# os20_newenc.net
KiCad netlist of a schematic drawn in EAGLE
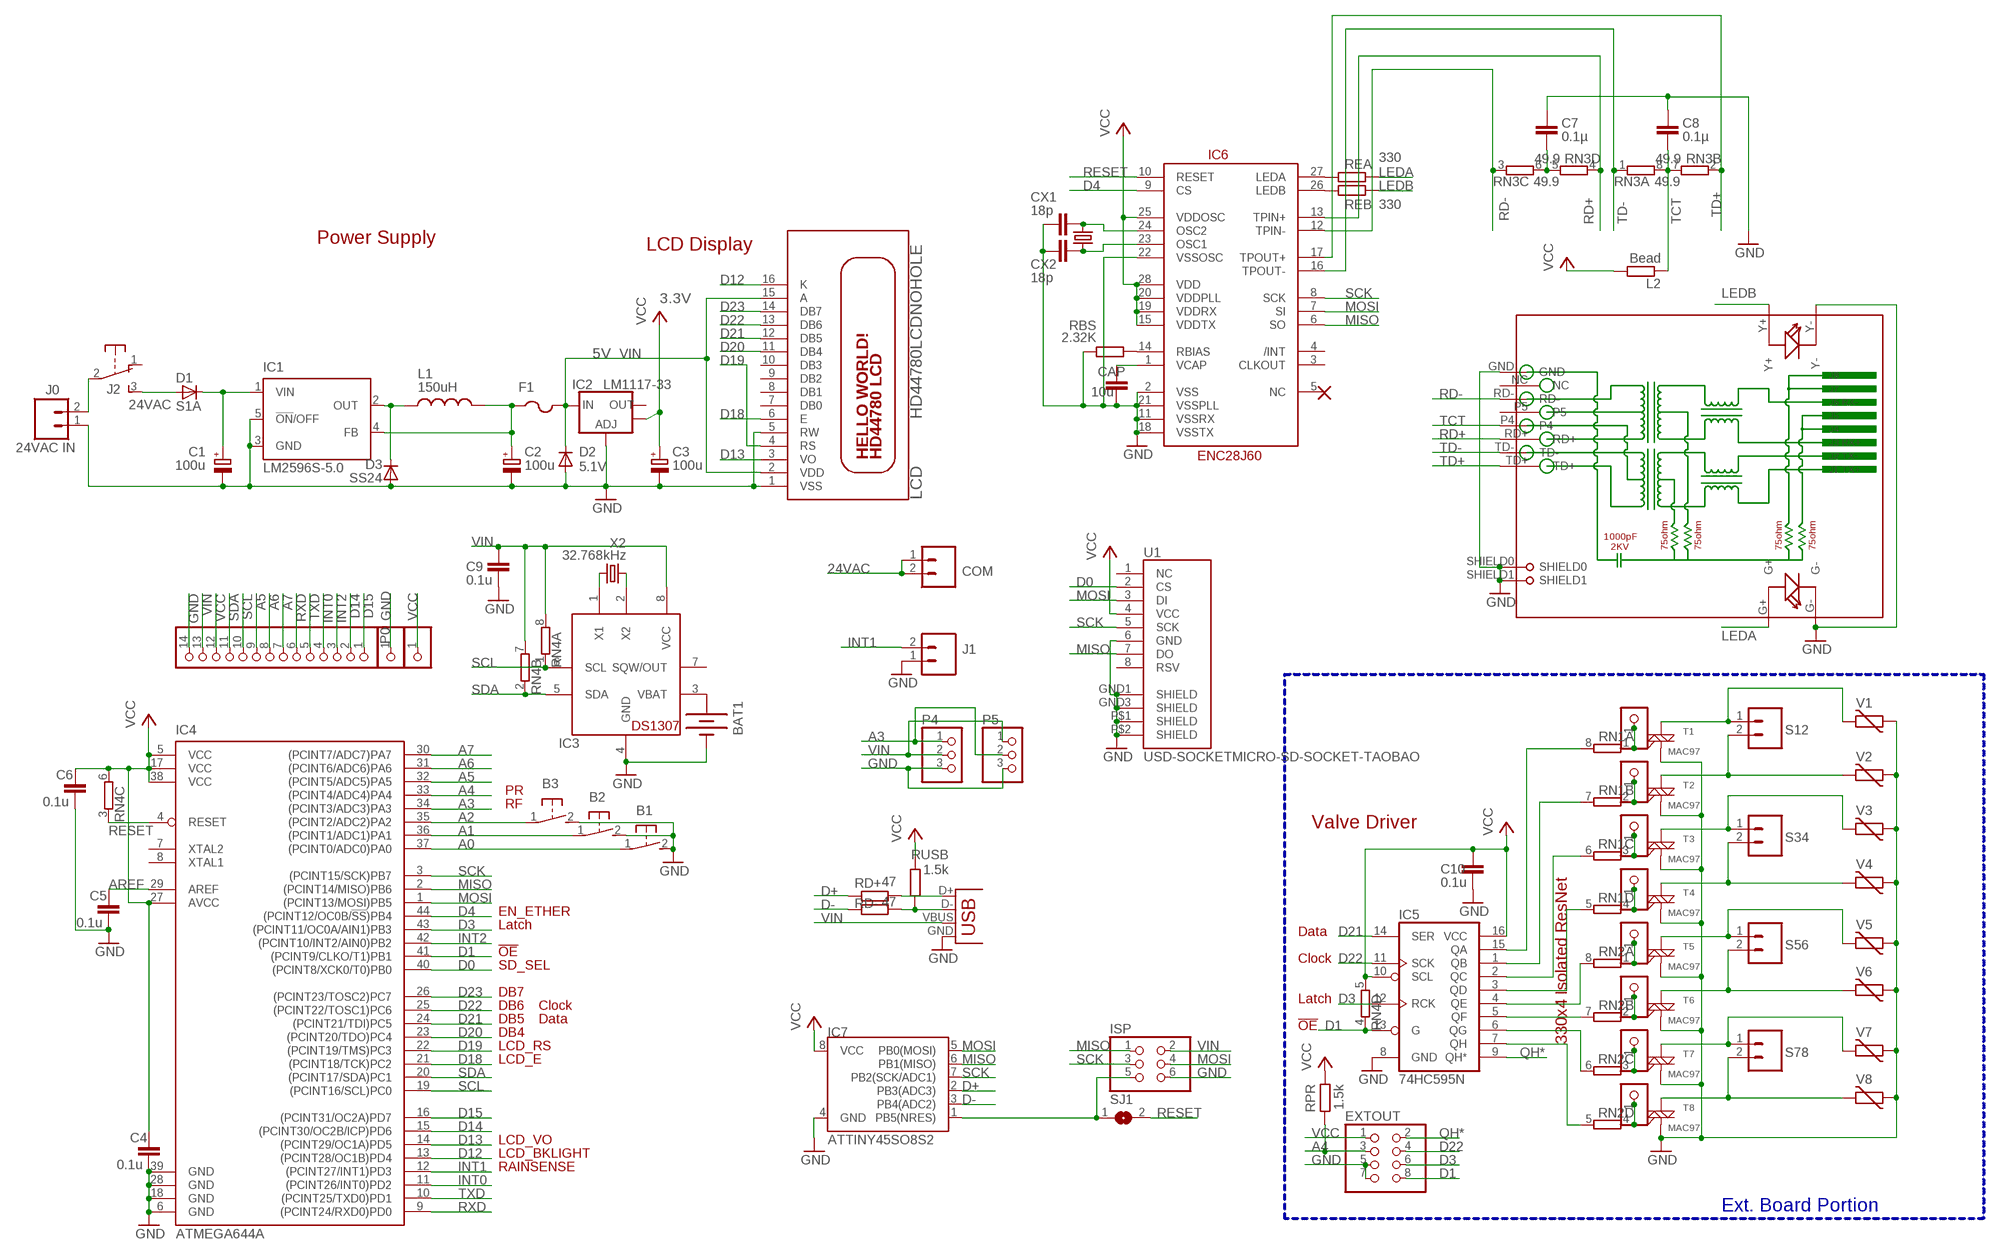
[diagram p0: schematic, sheet 1]

(export (version "E")
  (design (tool "Eeschema 10.0.6"))
  (components
    (comp (ref "B1")
      (value "31-XX")
      (footprint "eagle-import:B3F-31XX")
      (libsource (lib "eagle-import") (part "31-XX"))
    )
    (comp (ref "B2")
      (value "31-XX")
      (footprint "eagle-import:B3F-31XX")
      (libsource (lib "eagle-import") (part "31-XX"))
    )
    (comp (ref "B3")
      (value "31-XX")
      (footprint "eagle-import:B3F-31XX")
      (libsource (lib "eagle-import") (part "31-XX"))
    )
    (comp (ref "BAT1")
      (value "BATTERYBATTERY_12MM_SMT")
      (footprint "eagle-import:BATTCON_12MM_SMT")
      (libsource (lib "eagle-import") (part "BATTERYBATTERY_12MM_SMT"))
    )
    (comp (ref "C1")
      (value "100u")
      (footprint "eagle-import:E3,5-8")
      (libsource (lib "eagle-import") (part "CPOL-EUE3.5-8"))
    )
    (comp (ref "C2")
      (value "100u")
      (footprint "eagle-import:PANASONIC_D")
      (libsource (lib "eagle-import") (part "CPOL-EUD"))
    )
    (comp (ref "C3")
      (value "100u")
      (footprint "eagle-import:PANASONIC_D")
      (libsource (lib "eagle-import") (part "CPOL-EUD"))
    )
    (comp (ref "C4")
      (value "0.1u")
      (footprint "eagle-import:C0805")
      (libsource (lib "eagle-import") (part "C-EUC0805"))
    )
    (comp (ref "C5")
      (value "0.1u")
      (footprint "eagle-import:C0805")
      (libsource (lib "eagle-import") (part "C-EUC0805"))
    )
    (comp (ref "C6")
      (value "0.1u")
      (footprint "eagle-import:C0805")
      (libsource (lib "eagle-import") (part "C-EUC0805"))
    )
    (comp (ref "C7")
      (value "0.1µ")
      (footprint "eagle-import:C0805")
      (libsource (lib "eagle-import") (part "resistor_C-EUC0805"))
    )
    (comp (ref "C8")
      (value "0.1µ")
      (footprint "eagle-import:C0805")
      (libsource (lib "eagle-import") (part "resistor_C-EUC0805"))
    )
    (comp (ref "C9")
      (value "0.1u")
      (footprint "eagle-import:C0805")
      (libsource (lib "eagle-import") (part "C-EUC0805"))
    )
    (comp (ref "C10")
      (value "0.1u")
      (footprint "eagle-import:C0805")
      (libsource (lib "eagle-import") (part "C-EUC0805"))
    )
    (comp (ref "CAP")
      (value "10u")
      (footprint "eagle-import:C0805")
      (libsource (lib "eagle-import") (part "resistor_C-EUC0805"))
    )
    (comp (ref "COM")
      (value "M025MM")
      (footprint "eagle-import:SCREWTERMINAL-5MM-2")
      (libsource (lib "eagle-import") (part "M025MM"))
    )
    (comp (ref "CX1")
      (value "18p")
      (footprint "eagle-import:C0805")
      (libsource (lib "eagle-import") (part "resistor_C-EUC0805"))
    )
    (comp (ref "CX2")
      (value "18p")
      (footprint "eagle-import:C0805")
      (libsource (lib "eagle-import") (part "resistor_C-EUC0805"))
    )
    (comp (ref "D1")
      (value "S1A")
      (footprint "eagle-import:DO-214AC")
      (libsource (lib "eagle-import") (part "DIODE-DO-214AC"))
    )
    (comp (ref "D2")
      (value "5.1V")
      (footprint "eagle-import:MINIMELF")
      (libsource (lib "eagle-import") (part "DIODE-MINIMELF"))
    )
    (comp (ref "D3")
      (value "SS24")
      (footprint "eagle-import:DO-214AC")
      (libsource (lib "eagle-import") (part "DIODE-DO-214AC"))
    )
    (comp (ref "EXTOUT")
      (value "PINHD-2X4")
      (footprint "eagle-import:2X04")
      (libsource (lib "eagle-import") (part "PINHD-2X4"))
    )
    (comp (ref "F1")
      (value "PTCFUSE-1812")
      (footprint "eagle-import:1812")
      (libsource (lib "eagle-import") (part "PTCFUSE-1812"))
    )
    (comp (ref "IC1")
      (value "LM2596S-5.0")
      (footprint "eagle-import:TO263-5")
      (fields (field (name "MF") "NATIONAL SEMICONDUCTOR") (field (name "MPN") "LM2596S-ADJ/NOPB"))
      (libsource (lib "eagle-import") (part "LM2596S"))
    )
    (comp (ref "IC2")
      (value "LM1117-33")
      (footprint "eagle-import:SOT223")
      (libsource (lib "eagle-import") (part "V_REG_LM1117SOT223"))
    )
    (comp (ref "IC3")
      (value "DS1307")
      (footprint "eagle-import:SO08")
      (libsource (lib "eagle-import") (part "DS1307SOIC"))
    )
    (comp (ref "IC4")
      (value "ATMEGA644A")
      (footprint "eagle-import:TQFP44")
      (fields (field (name "MPN") "ATMEGA644PV-10AU"))
      (libsource (lib "eagle-import") (part "ATMEGA644A"))
    )
    (comp (ref "IC5")
      (value "74HC595N")
      (footprint "eagle-import:SO16")
      (libsource (lib "eagle-import") (part "74595DLS"))
    )
    (comp (ref "IC6")
      (value "ENC28J60")
      (footprint "eagle-import:SOIC28WLONG")
      (libsource (lib "eagle-import") (part "ENC28J60SO28LONG"))
    )
    (comp (ref "IC7")
      (value "ATTINY45SO8S2")
      (footprint "eagle-import:SO8S2")
      (libsource (lib "eagle-import") (part "ATTINY45SO8S2"))
    )
    (comp (ref "ISP")
      (value "PINHD-2X3")
      (footprint "eagle-import:2X03")
      (libsource (lib "eagle-import") (part "PINHD-2X3"))
    )
    (comp (ref "J0")
      (value "24VAC IN")
      (footprint "eagle-import:SCREWTERMINAL-5MM-2")
      (libsource (lib "eagle-import") (part "M025MM"))
    )
    (comp (ref "J1")
      (value "M025MM")
      (footprint "eagle-import:SCREWTERMINAL-5MM-2")
      (libsource (lib "eagle-import") (part "M025MM"))
    )
    (comp (ref "J2")
      (value "EG1206")
      (footprint "eagle-import:EG1206")
      (libsource (lib "eagle-import") (part "EG1206"))
    )
    (comp (ref "JP2")
      (value "PINHD-1X1CB")
      (footprint "eagle-import:1X01-CLEANBIG")
      (libsource (lib "eagle-import") (part "PINHD-1X1CB"))
    )
    (comp (ref "JP3")
      (value "PINHD-1X1CB")
      (footprint "eagle-import:1X01-CLEANBIG")
      (libsource (lib "eagle-import") (part "PINHD-1X1CB"))
    )
    (comp (ref "JP4")
      (value "PINHD-1X1CB")
      (footprint "eagle-import:1X01-CLEANBIG")
      (libsource (lib "eagle-import") (part "PINHD-1X1CB"))
    )
    (comp (ref "JP5")
      (value "PINHD-1X1CB")
      (footprint "eagle-import:1X01-CLEANBIG")
      (libsource (lib "eagle-import") (part "PINHD-1X1CB"))
    )
    (comp (ref "JP6")
      (value "PINHD-1X1CB")
      (footprint "eagle-import:1X01-CLEANBIG")
      (libsource (lib "eagle-import") (part "PINHD-1X1CB"))
    )
    (comp (ref "JP7")
      (value "PINHD-1X1CB")
      (footprint "eagle-import:1X01-CLEANBIG")
      (libsource (lib "eagle-import") (part "PINHD-1X1CB"))
    )
    (comp (ref "JP8")
      (value "PINHD-1X1CB")
      (footprint "eagle-import:1X01-CLEANBIG")
      (libsource (lib "eagle-import") (part "PINHD-1X1CB"))
    )
    (comp (ref "JP9")
      (value "PINHD-1X1CB")
      (footprint "eagle-import:1X01-CLEANBIG")
      (libsource (lib "eagle-import") (part "PINHD-1X1CB"))
    )
    (comp (ref "L1")
      (value "150uH")
      (footprint "eagle-import:CDRH125")
      (libsource (lib "eagle-import") (part "INDUCTORPWR"))
    )
    (comp (ref "L2")
      (value "Bead")
      (footprint "eagle-import:R0805")
      (libsource (lib "eagle-import") (part "R-EU_R0805"))
    )
    (comp (ref "LCD")
      (value "HD44780LCDNOHOLE")
      (footprint "eagle-import:LCD1602A")
      (libsource (lib "eagle-import") (part "HD44780LCDNOHOLE"))
    )
    (comp (ref "P0")
      (value "PINHD-1X14-CB")
      (footprint "eagle-import:1X14-CB")
      (libsource (lib "eagle-import") (part "PINHD-1X14-CB"))
    )
    (comp (ref "P1")
      (value "PINHD-1X1CB")
      (footprint "eagle-import:1X01-CLEANBIG")
      (libsource (lib "eagle-import") (part "PINHD-1X1CB"))
    )
    (comp (ref "P2")
      (value "PINHD-1X1CB")
      (footprint "eagle-import:1X01-CLEANBIG")
      (libsource (lib "eagle-import") (part "PINHD-1X1CB"))
    )
    (comp (ref "P4")
      (value "PINHD-1X3")
      (footprint "eagle-import:1X03")
      (libsource (lib "eagle-import") (part "PINHD-1X3"))
    )
    (comp (ref "P5")
      (value "PINHD-1X3")
      (footprint "eagle-import:1X03")
      (libsource (lib "eagle-import") (part "PINHD-1X3"))
    )
    (comp (ref "RBS")
      (value "2.32K")
      (footprint "eagle-import:R0805")
      (libsource (lib "eagle-import") (part "R-EU_R0805"))
    )
    (comp (ref "RD+")
      (value "47")
      (footprint "eagle-import:R0805")
      (libsource (lib "eagle-import") (part "R-EU_R0805"))
    )
    (comp (ref "RD-")
      (value "47")
      (footprint "eagle-import:R0805")
      (libsource (lib "eagle-import") (part "R-EU_R0805"))
    )
    (comp (ref "REA")
      (value "330")
      (footprint "eagle-import:R0805")
      (libsource (lib "eagle-import") (part "R-EU_R0805"))
    )
    (comp (ref "REB")
      (value "330")
      (footprint "eagle-import:R0805")
      (libsource (lib "eagle-import") (part "R-EU_R0805"))
    )
    (comp (ref "RJ45")
      (value "HR911105A")
      (footprint "eagle-import:HR911105A")
      (libsource (lib "eagle-import") (part "HR911105A"))
    )
    (comp (ref "RN1")
      (value "4R-NEXB38V")
      (footprint "eagle-import:EXB38V")
      (libsource (lib "eagle-import") (part "4R-NEXB38V"))
    )
    (comp (ref "RN2")
      (value "4R-NEXB38V")
      (footprint "eagle-import:EXB38V")
      (libsource (lib "eagle-import") (part "4R-NEXB38V"))
    )
    (comp (ref "RN3")
      (value "49.9")
      (footprint "eagle-import:EXB38V")
      (libsource (lib "eagle-import") (part "4R-NEXB38V"))
    )
    (comp (ref "RN4")
      (value "4R-NEXB38V")
      (footprint "eagle-import:EXB38V")
      (libsource (lib "eagle-import") (part "4R-NEXB38V"))
    )
    (comp (ref "RPR")
      (value "1.5k")
      (footprint "eagle-import:R0805")
      (libsource (lib "eagle-import") (part "R-EU_R0805"))
    )
    (comp (ref "RUSB")
      (value "1.5k")
      (footprint "eagle-import:R0805")
      (libsource (lib "eagle-import") (part "R-EU_R0805"))
    )
    (comp (ref "S12")
      (value "M025MM")
      (footprint "eagle-import:SCREWTERMINAL-5MM-2")
      (libsource (lib "eagle-import") (part "M025MM"))
    )
    (comp (ref "S34")
      (value "M025MM")
      (footprint "eagle-import:SCREWTERMINAL-5MM-2")
      (libsource (lib "eagle-import") (part "M025MM"))
    )
    (comp (ref "S56")
      (value "M025MM")
      (footprint "eagle-import:SCREWTERMINAL-5MM-2")
      (libsource (lib "eagle-import") (part "M025MM"))
    )
    (comp (ref "S78")
      (value "M025MM")
      (footprint "eagle-import:SCREWTERMINAL-5MM-2")
      (libsource (lib "eagle-import") (part "M025MM"))
    )
    (comp (ref "SJ1") (value "SJ") (footprint "eagle-import:SJ") (libsource (lib "eagle-import") (part "SJ")))
    (comp (ref "T1")
      (value "MAC97")
      (footprint "eagle-import:SOT223")
      (libsource (lib "eagle-import") (part "MAC97SOT223"))
    )
    (comp (ref "T2")
      (value "MAC97")
      (footprint "eagle-import:SOT223")
      (libsource (lib "eagle-import") (part "MAC97SOT223"))
    )
    (comp (ref "T3")
      (value "MAC97")
      (footprint "eagle-import:SOT223")
      (libsource (lib "eagle-import") (part "MAC97SOT223"))
    )
    (comp (ref "T4")
      (value "MAC97")
      (footprint "eagle-import:SOT223")
      (libsource (lib "eagle-import") (part "MAC97SOT223"))
    )
    (comp (ref "T5")
      (value "MAC97")
      (footprint "eagle-import:SOT223")
      (libsource (lib "eagle-import") (part "MAC97SOT223"))
    )
    (comp (ref "T6")
      (value "MAC97")
      (footprint "eagle-import:SOT223")
      (libsource (lib "eagle-import") (part "MAC97SOT223"))
    )
    (comp (ref "T7")
      (value "MAC97")
      (footprint "eagle-import:SOT223")
      (libsource (lib "eagle-import") (part "MAC97SOT223"))
    )
    (comp (ref "T8")
      (value "MAC97")
      (footprint "eagle-import:SOT223")
      (libsource (lib "eagle-import") (part "MAC97SOT223"))
    )
    (comp (ref "U1")
      (value "USD-SOCKETMICRO-SD-SOCKET-TAOBAO")
      (footprint "eagle-import:MICRO-SD-SOCKET-TAOBAO")
      (libsource (lib "eagle-import") (part "USD-SOCKETMICRO-SD-SOCKET-TAOBAO"))
    )
    (comp (ref "USB")
      (value "USBPTH")
      (footprint "eagle-import:USB-B-PTH")
      (libsource (lib "eagle-import") (part "USBPTH"))
    )
    (comp (ref "V1")
      (value "MOV")
      (footprint "eagle-import:R-5")
      (libsource (lib "eagle-import") (part "VARISTOR-5"))
    )
    (comp (ref "V2")
      (value "MOV")
      (footprint "eagle-import:R-5")
      (libsource (lib "eagle-import") (part "VARISTOR-5"))
    )
    (comp (ref "V3")
      (value "MOV")
      (footprint "eagle-import:R-5")
      (libsource (lib "eagle-import") (part "VARISTOR-5"))
    )
    (comp (ref "V4")
      (value "MOV")
      (footprint "eagle-import:R-5")
      (libsource (lib "eagle-import") (part "VARISTOR-5"))
    )
    (comp (ref "V5")
      (value "MOV")
      (footprint "eagle-import:R-5")
      (libsource (lib "eagle-import") (part "VARISTOR-5"))
    )
    (comp (ref "V6")
      (value "MOV")
      (footprint "eagle-import:R-5")
      (libsource (lib "eagle-import") (part "VARISTOR-5"))
    )
    (comp (ref "V7")
      (value "MOV")
      (footprint "eagle-import:R-5")
      (libsource (lib "eagle-import") (part "VARISTOR-5"))
    )
    (comp (ref "V8")
      (value "MOV")
      (footprint "eagle-import:R-5")
      (libsource (lib "eagle-import") (part "VARISTOR-5"))
    )
    (comp (ref "X1")
      (value "25MHz")
      (footprint "eagle-import:HC49US")
      (libsource (lib "eagle-import") (part "CRYSTALHC49US"))
    )
    (comp (ref "X2")
      (value "32.768kHz")
      (footprint "eagle-import:TC26H")
      (libsource (lib "eagle-import") (part "crystal_CRYSTALTC26H"))
    )
  )
  (nets
    (net (code "1") (name "/24VAC") (class "Default")
      (node (ref "COM") (pin "1") (pinfunction "1_1") (pintype "passive"))
      (node (ref "COM") (pin "2") (pinfunction "2_2") (pintype "passive"))
      (node (ref "D1") (pin "A") (pinfunction "A_A") (pintype "passive"))
      (node (ref "J2") (pin "3") (pinfunction "S_3") (pintype "passive"))
    )
    (net (code "2") (name "/A0") (class "Default")
      (node (ref "B1") (pin "1") (pinfunction "P_1") (pintype "passive"))
      (node (ref "IC4") (pin "37") (pinfunction "(PCINT0/ADC0)PA0_37") (pintype "bidirectional"))
    )
    (net (code "3") (name "/A1") (class "Default")
      (node (ref "B2") (pin "1") (pinfunction "P_1") (pintype "passive"))
      (node (ref "IC4") (pin "36") (pinfunction "(PCINT1/ADC1)PA1_36") (pintype "bidirectional"))
    )
    (net (code "4") (name "/A2") (class "Default")
      (node (ref "B3") (pin "1") (pinfunction "P_1") (pintype "passive"))
      (node (ref "IC4") (pin "35") (pinfunction "(PCINT2/ADC2)PA2_35") (pintype "bidirectional"))
    )
    (net (code "5") (name "/A3") (class "Default")
      (node (ref "IC4") (pin "34") (pinfunction "(PCINT3/ADC3)PA3_34") (pintype "bidirectional"))
      (node (ref "P4") (pin "1") (pinfunction "1_1") (pintype "passive"))
      (node (ref "P5") (pin "2") (pinfunction "2_2") (pintype "passive"))
    )
    (net (code "6") (name "/A4") (class "Default")
      (node (ref "EXTOUT") (pin "3") (pinfunction "3_3") (pintype "passive"))
      (node (ref "IC4") (pin "33") (pinfunction "(PCINT4/ADC4)PA4_33") (pintype "bidirectional"))
      (node (ref "RPR") (pin "1") (pinfunction "1_1") (pintype "passive"))
    )
    (net (code "7") (name "/A5") (class "Default")
      (node (ref "IC4") (pin "32") (pinfunction "(PCINT5/ADC5)PA5_32") (pintype "bidirectional"))
      (node (ref "P0") (pin "9") (pinfunction "9_9") (pintype "passive"))
    )
    (net (code "8") (name "/A6") (class "Default")
      (node (ref "IC4") (pin "31") (pinfunction "(PCINT6/ADC6)PA6_31") (pintype "bidirectional"))
      (node (ref "P0") (pin "8") (pinfunction "8_8") (pintype "passive"))
    )
    (net (code "9") (name "/A7") (class "Default")
      (node (ref "IC4") (pin "30") (pinfunction "(PCINT7/ADC7)PA7_30") (pintype "bidirectional"))
      (node (ref "P0") (pin "7") (pinfunction "7_7") (pintype "passive"))
    )
    (net (code "10") (name "/AREF") (class "Default")
      (node (ref "C5") (pin "1") (pinfunction "1_1") (pintype "passive"))
      (node (ref "IC4") (pin "29") (pinfunction "AREF_29") (pintype "passive"))
    )
    (net (code "11") (name "/D+") (class "Default")
      (node (ref "IC7") (pin "2") (pinfunction "PB3(ADC3)_2") (pintype "bidirectional"))
      (node (ref "RD+") (pin "1") (pinfunction "1_1") (pintype "passive"))
    )
    (net (code "12") (name "/D-") (class "Default")
      (node (ref "IC7") (pin "3") (pinfunction "PB4(ADC2)_3") (pintype "bidirectional"))
      (node (ref "RD-") (pin "1") (pinfunction "1_1") (pintype "passive"))
    )
    (net (code "13") (name "/D0") (class "Default")
      (node (ref "IC4") (pin "40") (pinfunction "(PCINT8/XCK0/T0)PB0_40") (pintype "bidirectional"))
      (node (ref "U1") (pin "2") (pinfunction "CS_2") (pintype "bidirectional"))
    )
    (net (code "14") (name "/D1") (class "Default")
      (node (ref "EXTOUT") (pin "8") (pinfunction "8_8") (pintype "passive"))
      (node (ref "IC4") (pin "41") (pinfunction "(PCINT9/CLKO/T1)PB1_41") (pintype "bidirectional"))
      (node (ref "IC5") (pin "13") (pinfunction "G_13") (pintype "input"))
      (node (ref "RN4") (pin "4") (pinfunction "1_4") (pintype "passive"))
    )
    (net (code "15") (name "/D3") (class "Default")
      (node (ref "EXTOUT") (pin "6") (pinfunction "6_6") (pintype "passive"))
      (node (ref "IC4") (pin "43") (pinfunction "(PCINT11/OC0A/AIN1)PB3_43") (pintype "bidirectional"))
      (node (ref "IC5") (pin "12") (pinfunction "RCK_12") (pintype "input"))
    )
    (net (code "16") (name "/D4") (class "Default")
      (node (ref "IC4") (pin "44") (pinfunction "(PCINT12/OC0B/~{SS})PB4_44") (pintype "bidirectional"))
      (node (ref "IC6") (pin "9") (pinfunction "CS_9") (pintype "bidirectional"))
    )
    (net (code "17") (name "/D12") (class "Default")
      (node (ref "IC4") (pin "13") (pinfunction "(PCINT28/OC1B)PD4_13") (pintype "bidirectional"))
      (node (ref "LCD") (pin "16") (pinfunction "K_16") (pintype "input"))
    )
    (net (code "18") (name "/D13") (class "Default")
      (node (ref "IC4") (pin "14") (pinfunction "(PCINT29/OC1A)PD5_14") (pintype "bidirectional"))
      (node (ref "LCD") (pin "3") (pinfunction "VO_3") (pintype "input"))
    )
    (net (code "19") (name "/D14") (class "Default")
      (node (ref "IC4") (pin "15") (pinfunction "(PCINT30/OC2B/ICP)PD6_15") (pintype "bidirectional"))
      (node (ref "P0") (pin "2") (pinfunction "2_2") (pintype "passive"))
    )
    (net (code "20") (name "/D15") (class "Default")
      (node (ref "IC4") (pin "16") (pinfunction "(PCINT31/OC2A)PD7_16") (pintype "bidirectional"))
      (node (ref "P0") (pin "1") (pinfunction "1_1") (pintype "passive"))
    )
    (net (code "21") (name "/D18") (class "Default")
      (node (ref "IC4") (pin "21") (pinfunction "(PCINT18/TCK)PC2_21") (pintype "output"))
      (node (ref "LCD") (pin "6") (pinfunction "E_6") (pintype "input"))
    )
    (net (code "22") (name "/D19") (class "Default")
      (node (ref "IC4") (pin "22") (pinfunction "(PCINT19/TMS)PC3_22") (pintype "output"))
      (node (ref "LCD") (pin "4") (pinfunction "RS_4") (pintype "input"))
    )
    (net (code "23") (name "/D20") (class "Default")
      (node (ref "IC4") (pin "23") (pinfunction "(PCINT20/TDO)PC4_23") (pintype "output"))
      (node (ref "LCD") (pin "11") (pinfunction "DB4_11") (pintype "bidirectional"))
    )
    (net (code "24") (name "/D21") (class "Default")
      (node (ref "IC4") (pin "24") (pinfunction "(PCINT21/TDI)PC5_24") (pintype "output"))
      (node (ref "IC5") (pin "14") (pinfunction "SER_14") (pintype "input"))
      (node (ref "LCD") (pin "12") (pinfunction "DB5_12") (pintype "bidirectional"))
    )
    (net (code "25") (name "/D22") (class "Default")
      (node (ref "EXTOUT") (pin "4") (pinfunction "4_4") (pintype "passive"))
      (node (ref "IC4") (pin "25") (pinfunction "(PCINT22/TOSC1)PC6_25") (pintype "output"))
      (node (ref "IC5") (pin "11") (pinfunction "SCK_11") (pintype "input"))
      (node (ref "LCD") (pin "13") (pinfunction "DB6_13") (pintype "bidirectional"))
    )
    (net (code "26") (name "/D23") (class "Default")
      (node (ref "IC4") (pin "26") (pinfunction "(PCINT23/TOSC2)PC7_26") (pintype "output"))
      (node (ref "LCD") (pin "14") (pinfunction "DB7_14") (pintype "bidirectional"))
    )
    (net (code "27") (name "/INT0") (class "Default")
      (node (ref "IC4") (pin "11") (pinfunction "(PCINT26/INT0)PD2_11") (pintype "bidirectional"))
      (node (ref "P0") (pin "4") (pinfunction "4_4") (pintype "passive"))
    )
    (net (code "28") (name "/INT1") (class "Default")
      (node (ref "IC4") (pin "12") (pinfunction "(PCINT27/INT1)PD3_12") (pintype "bidirectional"))
      (node (ref "J1") (pin "2") (pinfunction "2_2") (pintype "passive"))
    )
    (net (code "29") (name "/INT2") (class "Default")
      (node (ref "IC4") (pin "42") (pinfunction "(PCINT10/INT2/AIN0)PB2_42") (pintype "bidirectional"))
      (node (ref "P0") (pin "3") (pinfunction "3_3") (pintype "passive"))
    )
    (net (code "30") (name "/LEDA") (class "Default")
      (node (ref "REA") (pin "2") (pinfunction "2_2") (pintype "passive"))
      (node (ref "RJ45") (pin "G+") (pinfunction "G+_G+") (pintype "bidirectional"))
    )
    (net (code "31") (name "/LEDB") (class "Default")
      (node (ref "REB") (pin "2") (pinfunction "2_2") (pintype "passive"))
      (node (ref "RJ45") (pin "Y+") (pinfunction "Y+_Y+") (pintype "bidirectional"))
    )
    (net (code "32") (name "/MISO") (class "Default")
      (node (ref "IC4") (pin "2") (pinfunction "(PCINT14/MISO)PB6_2") (pintype "bidirectional"))
      (node (ref "IC6") (pin "6") (pinfunction "SO_6") (pintype "bidirectional"))
      (node (ref "IC7") (pin "6") (pinfunction "PB1(MISO)_6") (pintype "bidirectional"))
      (node (ref "ISP") (pin "1") (pinfunction "1_1") (pintype "passive"))
      (node (ref "U1") (pin "7") (pinfunction "DO_7") (pintype "bidirectional"))
    )
    (net (code "33") (name "/MOSI") (class "Default")
      (node (ref "IC4") (pin "1") (pinfunction "(PCINT13/MOSI)PB5_1") (pintype "bidirectional"))
      (node (ref "IC6") (pin "7") (pinfunction "SI_7") (pintype "bidirectional"))
      (node (ref "IC7") (pin "5") (pinfunction "PB0(MOSI)_5") (pintype "bidirectional"))
      (node (ref "ISP") (pin "4") (pinfunction "4_4") (pintype "passive"))
      (node (ref "U1") (pin "3") (pinfunction "DI_3") (pintype "bidirectional"))
    )
    (net (code "34") (name "/QH*") (class "Default")
      (node (ref "EXTOUT") (pin "2") (pinfunction "2_2") (pintype "passive"))
      (node (ref "IC5") (pin "9") (pinfunction "QH*_9") (pintype "tri_state"))
    )
    (net (code "35") (name "/RD+") (class "Default")
      (node (ref "IC6") (pin "13") (pinfunction "TPIN+_13") (pintype "bidirectional"))
      (node (ref "RJ45") (pin "RD+") (pinfunction "RD+_RD+") (pintype "bidirectional"))
      (node (ref "RN3") (pin "4") (pinfunction "1_4") (pintype "passive"))
    )
    (net (code "36") (name "/RD-") (class "Default")
      (node (ref "IC6") (pin "12") (pinfunction "TPIN-_12") (pintype "bidirectional"))
      (node (ref "RJ45") (pin "RD-") (pinfunction "RD-_RD-") (pintype "bidirectional"))
      (node (ref "RN3") (pin "3") (pinfunction "1_3") (pintype "passive"))
    )
    (net (code "37") (name "/RESET") (class "Default")
      (node (ref "IC4") (pin "4") (pinfunction "RESET_4") (pintype "input"))
      (node (ref "IC6") (pin "10") (pinfunction "RESET_10") (pintype "bidirectional"))
      (node (ref "RN4") (pin "3") (pinfunction "1_3") (pintype "passive"))
      (node (ref "SJ1") (pin "2") (pinfunction "2_2") (pintype "passive"))
    )
    (net (code "38") (name "/RXD") (class "Default")
      (node (ref "IC4") (pin "9") (pinfunction "(PCINT24/RXD0)PD0_9") (pintype "bidirectional"))
      (node (ref "P0") (pin "6") (pinfunction "6_6") (pintype "passive"))
    )
    (net (code "39") (name "/SCK") (class "Default")
      (node (ref "IC4") (pin "3") (pinfunction "(PCINT15/SCK)PB7_3") (pintype "bidirectional"))
      (node (ref "IC6") (pin "8") (pinfunction "SCK_8") (pintype "bidirectional"))
      (node (ref "IC7") (pin "7") (pinfunction "PB2(SCK/ADC1)_7") (pintype "bidirectional"))
      (node (ref "ISP") (pin "3") (pinfunction "3_3") (pintype "passive"))
      (node (ref "U1") (pin "5") (pinfunction "SCK_5") (pintype "bidirectional"))
    )
    (net (code "40") (name "/SCL") (class "Default")
      (node (ref "IC3") (pin "6") (pinfunction "SCL_6") (pintype "bidirectional"))
      (node (ref "IC4") (pin "19") (pinfunction "(PCINT16/SCL)PC0_19") (pintype "output"))
      (node (ref "P0") (pin "10") (pinfunction "10_10") (pintype "passive"))
      (node (ref "RN4") (pin "1") (pinfunction "1_1") (pintype "passive"))
    )
    (net (code "41") (name "/SDA") (class "Default")
      (node (ref "IC3") (pin "5") (pinfunction "SDA_5") (pintype "bidirectional"))
      (node (ref "IC4") (pin "20") (pinfunction "(PCINT17/SDA)PC1_20") (pintype "output"))
      (node (ref "P0") (pin "11") (pinfunction "11_11") (pintype "passive"))
      (node (ref "RN4") (pin "2") (pinfunction "1_2") (pintype "passive"))
    )
    (net (code "42") (name "/TCT") (class "Default")
      (node (ref "C8") (pin "2") (pinfunction "2_2") (pintype "passive"))
      (node (ref "L2") (pin "1") (pinfunction "1_1") (pintype "passive"))
      (node (ref "RJ45") (pin "P4") (pinfunction "P4_P4") (pintype "bidirectional"))
      (node (ref "RN3") (pin "7") (pinfunction "2_7") (pintype "passive"))
      (node (ref "RN3") (pin "8") (pinfunction "2_8") (pintype "passive"))
    )
    (net (code "43") (name "/TD+") (class "Default")
      (node (ref "IC6") (pin "17") (pinfunction "TPOUT+_17") (pintype "bidirectional"))
      (node (ref "RJ45") (pin "TD+") (pinfunction "TD+_TD+") (pintype "bidirectional"))
      (node (ref "RN3") (pin "2") (pinfunction "1_2") (pintype "passive"))
    )
    (net (code "44") (name "/TD-") (class "Default")
      (node (ref "IC6") (pin "16") (pinfunction "TPOUT-_16") (pintype "bidirectional"))
      (node (ref "RJ45") (pin "TD-") (pinfunction "TD-_TD-") (pintype "bidirectional"))
      (node (ref "RN3") (pin "1") (pinfunction "1_1") (pintype "passive"))
    )
    (net (code "45") (name "/TXD") (class "Default")
      (node (ref "IC4") (pin "10") (pinfunction "(PCINT25/TXD0)PD1_10") (pintype "bidirectional"))
      (node (ref "P0") (pin "5") (pinfunction "5_5") (pintype "passive"))
    )
    (net (code "46") (name "/VIN") (class "Default")
      (node (ref "C9") (pin "1") (pinfunction "1_1") (pintype "passive"))
      (node (ref "D2") (pin "C") (pinfunction "C_C") (pintype "passive"))
      (node (ref "F1") (pin "2") (pinfunction "2_2") (pintype "passive"))
      (node (ref "IC2") (pin "3") (pinfunction "IN_3") (pintype "input"))
      (node (ref "IC3") (pin "8") (pinfunction "VCC_8") (pintype "power_in"))
      (node (ref "ISP") (pin "2") (pinfunction "2_2") (pintype "passive"))
      (node (ref "LCD") (pin "15") (pinfunction "A_15") (pintype "input"))
      (node (ref "LCD") (pin "2") (pinfunction "VDD_2") (pintype "power_in"))
      (node (ref "P0") (pin "13") (pinfunction "13_13") (pintype "passive"))
      (node (ref "P4") (pin "2") (pinfunction "2_2") (pintype "passive"))
      (node (ref "P5") (pin "1") (pinfunction "1_1") (pintype "passive"))
      (node (ref "RN4") (pin "7") (pinfunction "2_7") (pintype "passive"))
      (node (ref "RN4") (pin "8") (pinfunction "2_8") (pintype "passive"))
      (node (ref "USB") (pin "VBUS") (pinfunction "VBUS_VBUS") (pintype "bidirectional"))
    )
    (net (code "47") (name "GND") (class "Default")
      (node (ref "B1") (pin "2") (pinfunction "S_2") (pintype "passive"))
      (node (ref "B2") (pin "2") (pinfunction "S_2") (pintype "passive"))
      (node (ref "B3") (pin "2") (pinfunction "S_2") (pintype "passive"))
      (node (ref "BAT1") (pin "P$1") (pinfunction "-_P$1") (pintype "power_in"))
      (node (ref "C1") (pin "-") (pinfunction "-_-") (pintype "passive"))
      (node (ref "C10") (pin "2") (pinfunction "2_2") (pintype "passive"))
      (node (ref "C2") (pin "-") (pinfunction "-_-") (pintype "passive"))
      (node (ref "C3") (pin "-") (pinfunction "-_-") (pintype "passive"))
      (node (ref "C4") (pin "2") (pinfunction "2_2") (pintype "passive"))
      (node (ref "C5") (pin "2") (pinfunction "2_2") (pintype "passive"))
      (node (ref "C6") (pin "2") (pinfunction "2_2") (pintype "passive"))
      (node (ref "C7") (pin "1") (pinfunction "1_1") (pintype "passive"))
      (node (ref "C8") (pin "1") (pinfunction "1_1") (pintype "passive"))
      (node (ref "C9") (pin "2") (pinfunction "2_2") (pintype "passive"))
      (node (ref "CAP") (pin "2") (pinfunction "2_2") (pintype "passive"))
      (node (ref "CX1") (pin "2") (pinfunction "2_2") (pintype "passive"))
      (node (ref "CX2") (pin "2") (pinfunction "2_2") (pintype "passive"))
      (node (ref "D2") (pin "A") (pinfunction "A_A") (pintype "passive"))
      (node (ref "D3") (pin "A") (pinfunction "A_A") (pintype "passive"))
      (node (ref "EXTOUT") (pin "5") (pinfunction "5_5") (pintype "passive"))
      (node (ref "EXTOUT") (pin "7") (pinfunction "7_7") (pintype "passive"))
      (node (ref "IC1") (pin "3") (pinfunction "GND_3") (pintype "power_in"))
      (node (ref "IC1") (pin "5") (pinfunction "~{ON}/OFF_5") (pintype "input"))
      (node (ref "IC2") (pin "1") (pinfunction "ADJ_1") (pintype "input"))
      (node (ref "IC3") (pin "4") (pinfunction "GND_4") (pintype "power_in"))
      (node (ref "IC4") (pin "18") (pinfunction "GND_18") (pintype "power_in"))
      (node (ref "IC4") (pin "28") (pinfunction "GND_28") (pintype "power_in"))
      (node (ref "IC4") (pin "39") (pinfunction "GND_39") (pintype "power_in"))
      (node (ref "IC4") (pin "6") (pinfunction "GND_6") (pintype "power_in"))
      (node (ref "IC5") (pin "8") (pinfunction "GND_8") (pintype "power_in"))
      (node (ref "IC6") (pin "11") (pinfunction "VSSRX_11") (pintype "bidirectional"))
      (node (ref "IC6") (pin "18") (pinfunction "VSSTX_18") (pintype "bidirectional"))
      (node (ref "IC6") (pin "2") (pinfunction "VSS_2") (pintype "bidirectional"))
      (node (ref "IC6") (pin "21") (pinfunction "VSSPLL_21") (pintype "bidirectional"))
      (node (ref "IC6") (pin "22") (pinfunction "VSSOSC_22") (pintype "bidirectional"))
      (node (ref "IC7") (pin "4") (pinfunction "GND_4") (pintype "bidirectional"))
      (node (ref "ISP") (pin "6") (pinfunction "6_6") (pintype "passive"))
      (node (ref "J0") (pin "1") (pinfunction "1_1") (pintype "passive"))
      (node (ref "J1") (pin "1") (pinfunction "1_1") (pintype "passive"))
      (node (ref "LCD") (pin "1") (pinfunction "VSS_1") (pintype "power_in"))
      (node (ref "LCD") (pin "5") (pinfunction "RW_5") (pintype "input"))
      (node (ref "P0") (pin "14") (pinfunction "14_14") (pintype "passive"))
      (node (ref "P1") (pin "1") (pinfunction "1_1") (pintype "passive"))
      (node (ref "P4") (pin "3") (pinfunction "3_3") (pintype "passive"))
      (node (ref "P5") (pin "3") (pinfunction "3_3") (pintype "passive"))
      (node (ref "RBS") (pin "1") (pinfunction "1_1") (pintype "passive"))
      (node (ref "RJ45") (pin "G-") (pinfunction "G-_G-") (pintype "bidirectional"))
      (node (ref "RJ45") (pin "GND") (pinfunction "GND_GND") (pintype "bidirectional"))
      (node (ref "RJ45") (pin "SHIELD0") (pinfunction "SHIELD0_SHIELD0") (pintype "bidirectional"))
      (node (ref "RJ45") (pin "SHIELD1") (pinfunction "SHIELD1_SHIELD1") (pintype "bidirectional"))
      (node (ref "RJ45") (pin "Y-") (pinfunction "Y-_Y-") (pintype "bidirectional"))
      (node (ref "T1") (pin "1") (pinfunction "M1_1") (pintype "bidirectional"))
      (node (ref "T2") (pin "1") (pinfunction "M1_1") (pintype "bidirectional"))
      (node (ref "T3") (pin "1") (pinfunction "M1_1") (pintype "bidirectional"))
      (node (ref "T4") (pin "1") (pinfunction "M1_1") (pintype "bidirectional"))
      (node (ref "T5") (pin "1") (pinfunction "M1_1") (pintype "bidirectional"))
      (node (ref "T6") (pin "1") (pinfunction "M1_1") (pintype "bidirectional"))
      (node (ref "T7") (pin "1") (pinfunction "M1_1") (pintype "bidirectional"))
      (node (ref "T8") (pin "1") (pinfunction "M1_1") (pintype "bidirectional"))
      (node (ref "U1") (pin "6") (pinfunction "GND_6") (pintype "bidirectional"))
      (node (ref "U1") (pin "GND1") (pinfunction "SHIELD_GND1") (pintype "bidirectional"))
      (node (ref "U1") (pin "GND3") (pinfunction "SHIELD_GND3") (pintype "bidirectional"))
      (node (ref "U1") (pin "P$1") (pinfunction "SHIELD_P$1") (pintype "bidirectional"))
      (node (ref "U1") (pin "P$2") (pinfunction "SHIELD_P$2") (pintype "bidirectional"))
      (node (ref "USB") (pin "GND") (pinfunction "GND_GND") (pintype "bidirectional"))
      (node (ref "V1") (pin "1") (pinfunction "1_1") (pintype "passive"))
      (node (ref "V2") (pin "1") (pinfunction "1_1") (pintype "passive"))
      (node (ref "V3") (pin "1") (pinfunction "1_1") (pintype "passive"))
      (node (ref "V4") (pin "1") (pinfunction "1_1") (pintype "passive"))
      (node (ref "V5") (pin "1") (pinfunction "1_1") (pintype "passive"))
      (node (ref "V6") (pin "1") (pinfunction "1_1") (pintype "passive"))
      (node (ref "V7") (pin "1") (pinfunction "1_1") (pintype "passive"))
      (node (ref "V8") (pin "1") (pinfunction "1_1") (pintype "passive"))
    )
    (net (code "48") (name "Net-(BAT1-+)") (class "Default")
      (node (ref "BAT1") (pin "P$2") (pinfunction "+_P$2") (pintype "power_in"))
      (node (ref "IC3") (pin "3") (pinfunction "VBAT_3") (pintype "power_in"))
    )
    (net (code "49") (name "Net-(IC1-FB)") (class "Default")
      (node (ref "C2") (pin "+") (pinfunction "+_+") (pintype "passive"))
      (node (ref "F1") (pin "1") (pinfunction "1_1") (pintype "passive"))
      (node (ref "IC1") (pin "4") (pinfunction "FB_4") (pintype "input"))
      (node (ref "L1") (pin "2") (pinfunction "2_2") (pintype "passive"))
    )
    (net (code "50") (name "Net-(IC1-OUT)") (class "Default")
      (node (ref "D3") (pin "C") (pinfunction "C_C") (pintype "passive"))
      (node (ref "IC1") (pin "2") (pinfunction "OUT_2") (pintype "output"))
      (node (ref "L1") (pin "1") (pinfunction "1_1") (pintype "passive"))
    )
    (net (code "51") (name "Net-(IC1-VIN)") (class "Default")
      (node (ref "C1") (pin "+") (pinfunction "+_+") (pintype "passive"))
      (node (ref "D1") (pin "C") (pinfunction "C_C") (pintype "passive"))
      (node (ref "IC1") (pin "1") (pinfunction "VIN_1") (pintype "input"))
    )
    (net (code "52") (name "Net-(IC3-X1)") (class "Default")
      (node (ref "IC3") (pin "1") (pinfunction "X1_1") (pintype "passive"))
      (node (ref "X2") (pin "2") (pinfunction "2_2") (pintype "passive"))
    )
    (net (code "53") (name "Net-(IC3-X2)") (class "Default")
      (node (ref "IC3") (pin "2") (pinfunction "X2_2") (pintype "passive"))
      (node (ref "X2") (pin "1") (pinfunction "1_1") (pintype "passive"))
    )
    (net (code "54") (name "Net-(IC5-QA)") (class "Default")
      (node (ref "IC5") (pin "15") (pinfunction "QA_15") (pintype "tri_state"))
      (node (ref "RN1") (pin "8") (pinfunction "2_8") (pintype "passive"))
    )
    (net (code "55") (name "Net-(IC5-QB)") (class "Default")
      (node (ref "IC5") (pin "1") (pinfunction "QB_1") (pintype "tri_state"))
      (node (ref "RN1") (pin "7") (pinfunction "2_7") (pintype "passive"))
    )
    (net (code "56") (name "Net-(IC5-QC)") (class "Default")
      (node (ref "IC5") (pin "2") (pinfunction "QC_2") (pintype "tri_state"))
      (node (ref "RN1") (pin "6") (pinfunction "2_6") (pintype "passive"))
    )
    (net (code "57") (name "Net-(IC5-QD)") (class "Default")
      (node (ref "IC5") (pin "3") (pinfunction "QD_3") (pintype "tri_state"))
      (node (ref "RN1") (pin "5") (pinfunction "2_5") (pintype "passive"))
    )
    (net (code "58") (name "Net-(IC5-QE)") (class "Default")
      (node (ref "IC5") (pin "4") (pinfunction "QE_4") (pintype "tri_state"))
      (node (ref "RN2") (pin "8") (pinfunction "2_8") (pintype "passive"))
    )
    (net (code "59") (name "Net-(IC5-QF)") (class "Default")
      (node (ref "IC5") (pin "5") (pinfunction "QF_5") (pintype "tri_state"))
      (node (ref "RN2") (pin "7") (pinfunction "2_7") (pintype "passive"))
    )
    (net (code "60") (name "Net-(IC5-QG)") (class "Default")
      (node (ref "IC5") (pin "6") (pinfunction "QG_6") (pintype "tri_state"))
      (node (ref "RN2") (pin "6") (pinfunction "2_6") (pintype "passive"))
    )
    (net (code "61") (name "Net-(IC5-QH)") (class "Default")
      (node (ref "IC5") (pin "7") (pinfunction "QH_7") (pintype "tri_state"))
      (node (ref "RN2") (pin "5") (pinfunction "2_5") (pintype "passive"))
    )
    (net (code "62") (name "Net-(IC6-LEDA)") (class "Default")
      (node (ref "IC6") (pin "27") (pinfunction "LEDA_27") (pintype "bidirectional"))
      (node (ref "REA") (pin "1") (pinfunction "1_1") (pintype "passive"))
    )
    (net (code "63") (name "Net-(IC6-LEDB)") (class "Default")
      (node (ref "IC6") (pin "26") (pinfunction "LEDB_26") (pintype "bidirectional"))
      (node (ref "REB") (pin "1") (pinfunction "1_1") (pintype "passive"))
    )
    (net (code "64") (name "Net-(IC6-OSC1)") (class "Default")
      (node (ref "CX2") (pin "1") (pinfunction "1_1") (pintype "passive"))
      (node (ref "IC6") (pin "23") (pinfunction "OSC1_23") (pintype "bidirectional"))
      (node (ref "X1") (pin "1") (pinfunction "1_1") (pintype "passive"))
    )
    (net (code "65") (name "Net-(IC6-OSC2)") (class "Default")
      (node (ref "CX1") (pin "1") (pinfunction "1_1") (pintype "passive"))
      (node (ref "IC6") (pin "24") (pinfunction "OSC2_24") (pintype "bidirectional"))
      (node (ref "X1") (pin "2") (pinfunction "2_2") (pintype "passive"))
    )
    (net (code "66") (name "Net-(IC6-RBIAS)") (class "Default")
      (node (ref "IC6") (pin "14") (pinfunction "RBIAS_14") (pintype "bidirectional"))
      (node (ref "RBS") (pin "2") (pinfunction "2_2") (pintype "passive"))
    )
    (net (code "67") (name "Net-(IC6-VCAP)") (class "Default")
      (node (ref "CAP") (pin "1") (pinfunction "1_1") (pintype "passive"))
      (node (ref "IC6") (pin "1") (pinfunction "VCAP_1") (pintype "bidirectional"))
    )
    (net (code "68") (name "Net-(IC7-PB5(NRES))") (class "Default")
      (node (ref "IC7") (pin "1") (pinfunction "PB5(NRES)_1") (pintype "bidirectional"))
      (node (ref "ISP") (pin "5") (pinfunction "5_5") (pintype "passive"))
      (node (ref "SJ1") (pin "1") (pinfunction "1_1") (pintype "passive"))
    )
    (net (code "69") (name "Net-(J2-P)") (class "Default")
      (node (ref "J0") (pin "2") (pinfunction "2_2") (pintype "passive"))
      (node (ref "J2") (pin "2") (pinfunction "P_2") (pintype "passive"))
    )
    (net (code "70") (name "Net-(RD+-Pad2)") (class "Default")
      (node (ref "RD+") (pin "2") (pinfunction "2_2") (pintype "passive"))
      (node (ref "USB") (pin "D+") (pinfunction "D+_D+") (pintype "bidirectional"))
    )
    (net (code "71") (name "Net-(RD--Pad2)") (class "Default")
      (node (ref "RD-") (pin "2") (pinfunction "2_2") (pintype "passive"))
      (node (ref "RUSB") (pin "1") (pinfunction "1_1") (pintype "passive"))
      (node (ref "USB") (pin "D-") (pinfunction "D-_D-") (pintype "bidirectional"))
    )
    (net (code "72") (name "Net-(RN1B-1)") (class "Default")
      (node (ref "JP3") (pin "1") (pinfunction "1_1") (pintype "passive"))
      (node (ref "RN1") (pin "2") (pinfunction "1_2") (pintype "passive"))
      (node (ref "T2") (pin "3") (pinfunction "G_3") (pintype "bidirectional"))
    )
    (net (code "73") (name "Net-(RN1C-1)") (class "Default")
      (node (ref "JP4") (pin "1") (pinfunction "1_1") (pintype "passive"))
      (node (ref "RN1") (pin "3") (pinfunction "1_3") (pintype "passive"))
      (node (ref "T3") (pin "3") (pinfunction "G_3") (pintype "bidirectional"))
    )
    (net (code "74") (name "Net-(RN1D-1)") (class "Default")
      (node (ref "JP5") (pin "1") (pinfunction "1_1") (pintype "passive"))
      (node (ref "RN1") (pin "4") (pinfunction "1_4") (pintype "passive"))
      (node (ref "T4") (pin "3") (pinfunction "G_3") (pintype "bidirectional"))
    )
    (net (code "75") (name "Net-(RN2B-1)") (class "Default")
      (node (ref "JP7") (pin "1") (pinfunction "1_1") (pintype "passive"))
      (node (ref "RN2") (pin "2") (pinfunction "1_2") (pintype "passive"))
      (node (ref "T6") (pin "3") (pinfunction "G_3") (pintype "bidirectional"))
    )
    (net (code "76") (name "Net-(RN2C-1)") (class "Default")
      (node (ref "JP8") (pin "1") (pinfunction "1_1") (pintype "passive"))
      (node (ref "RN2") (pin "3") (pinfunction "1_3") (pintype "passive"))
      (node (ref "T7") (pin "3") (pinfunction "G_3") (pintype "bidirectional"))
    )
    (net (code "77") (name "Net-(RN2D-1)") (class "Default")
      (node (ref "JP9") (pin "1") (pinfunction "1_1") (pintype "passive"))
      (node (ref "RN2") (pin "4") (pinfunction "1_4") (pintype "passive"))
      (node (ref "T8") (pin "3") (pinfunction "G_3") (pintype "bidirectional"))
    )
    (net (code "78") (name "Net-(RN3C-2)") (class "Default")
      (node (ref "C7") (pin "2") (pinfunction "2_2") (pintype "passive"))
      (node (ref "RN3") (pin "5") (pinfunction "2_5") (pintype "passive"))
      (node (ref "RN3") (pin "6") (pinfunction "2_6") (pintype "passive"))
    )
    (net (code "79") (name "Net-(T1-G)") (class "Default")
      (node (ref "JP2") (pin "1") (pinfunction "1_1") (pintype "passive"))
      (node (ref "RN1") (pin "1") (pinfunction "1_1") (pintype "passive"))
      (node (ref "T1") (pin "3") (pinfunction "G_3") (pintype "bidirectional"))
    )
    (net (code "80") (name "Net-(T1-M2)") (class "Default")
      (node (ref "S12") (pin "1") (pinfunction "1_1") (pintype "passive"))
      (node (ref "T1") (pin "4") (pinfunction "M2_4") (pintype "bidirectional"))
      (node (ref "V1") (pin "2") (pinfunction "2_2") (pintype "passive"))
    )
    (net (code "81") (name "Net-(T2-M2)") (class "Default")
      (node (ref "S12") (pin "2") (pinfunction "2_2") (pintype "passive"))
      (node (ref "T2") (pin "4") (pinfunction "M2_4") (pintype "bidirectional"))
      (node (ref "V2") (pin "2") (pinfunction "2_2") (pintype "passive"))
    )
    (net (code "82") (name "Net-(T3-M2)") (class "Default")
      (node (ref "S34") (pin "1") (pinfunction "1_1") (pintype "passive"))
      (node (ref "T3") (pin "4") (pinfunction "M2_4") (pintype "bidirectional"))
      (node (ref "V3") (pin "2") (pinfunction "2_2") (pintype "passive"))
    )
    (net (code "83") (name "Net-(T4-M2)") (class "Default")
      (node (ref "S34") (pin "2") (pinfunction "2_2") (pintype "passive"))
      (node (ref "T4") (pin "4") (pinfunction "M2_4") (pintype "bidirectional"))
      (node (ref "V4") (pin "2") (pinfunction "2_2") (pintype "passive"))
    )
    (net (code "84") (name "Net-(T5-G)") (class "Default")
      (node (ref "JP6") (pin "1") (pinfunction "1_1") (pintype "passive"))
      (node (ref "RN2") (pin "1") (pinfunction "1_1") (pintype "passive"))
      (node (ref "T5") (pin "3") (pinfunction "G_3") (pintype "bidirectional"))
    )
    (net (code "85") (name "Net-(T5-M2)") (class "Default")
      (node (ref "S56") (pin "1") (pinfunction "1_1") (pintype "passive"))
      (node (ref "T5") (pin "4") (pinfunction "M2_4") (pintype "bidirectional"))
      (node (ref "V5") (pin "2") (pinfunction "2_2") (pintype "passive"))
    )
    (net (code "86") (name "Net-(T6-M2)") (class "Default")
      (node (ref "S56") (pin "2") (pinfunction "2_2") (pintype "passive"))
      (node (ref "T6") (pin "4") (pinfunction "M2_4") (pintype "bidirectional"))
      (node (ref "V6") (pin "2") (pinfunction "2_2") (pintype "passive"))
    )
    (net (code "87") (name "Net-(T7-M2)") (class "Default")
      (node (ref "S78") (pin "1") (pinfunction "1_1") (pintype "passive"))
      (node (ref "T7") (pin "4") (pinfunction "M2_4") (pintype "bidirectional"))
      (node (ref "V7") (pin "2") (pinfunction "2_2") (pintype "passive"))
    )
    (net (code "88") (name "Net-(T8-M2)") (class "Default")
      (node (ref "S78") (pin "2") (pinfunction "2_2") (pintype "passive"))
      (node (ref "T8") (pin "4") (pinfunction "M2_4") (pintype "bidirectional"))
      (node (ref "V8") (pin "2") (pinfunction "2_2") (pintype "passive"))
    )
    (net (code "89") (name "VCC") (class "Default")
      (node (ref "C10") (pin "1") (pinfunction "1_1") (pintype "passive"))
      (node (ref "C3") (pin "+") (pinfunction "+_+") (pintype "passive"))
      (node (ref "C4") (pin "1") (pinfunction "1_1") (pintype "passive"))
      (node (ref "C6") (pin "1") (pinfunction "1_1") (pintype "passive"))
      (node (ref "EXTOUT") (pin "1") (pinfunction "1_1") (pintype "passive"))
      (node (ref "IC2") (pin "4") (pinfunction "OUT_4") (pintype "bidirectional"))
      (node (ref "IC4") (pin "17") (pinfunction "VCC_17") (pintype "power_in"))
      (node (ref "IC4") (pin "27") (pinfunction "AVCC_27") (pintype "power_in"))
      (node (ref "IC4") (pin "38") (pinfunction "VCC_38") (pintype "power_in"))
      (node (ref "IC4") (pin "5") (pinfunction "VCC_5") (pintype "power_in"))
      (node (ref "IC5") (pin "10") (pinfunction "SCL_10") (pintype "input"))
      (node (ref "IC5") (pin "16") (pinfunction "VCC_16") (pintype "power_in"))
      (node (ref "IC6") (pin "15") (pinfunction "VDDTX_15") (pintype "bidirectional"))
      (node (ref "IC6") (pin "19") (pinfunction "VDDRX_19") (pintype "bidirectional"))
      (node (ref "IC6") (pin "20") (pinfunction "VDDPLL_20") (pintype "bidirectional"))
      (node (ref "IC6") (pin "25") (pinfunction "VDDOSC_25") (pintype "bidirectional"))
      (node (ref "IC6") (pin "28") (pinfunction "VDD_28") (pintype "bidirectional"))
      (node (ref "IC7") (pin "8") (pinfunction "VCC_8") (pintype "bidirectional"))
      (node (ref "L2") (pin "2") (pinfunction "2_2") (pintype "passive"))
      (node (ref "P0") (pin "12") (pinfunction "12_12") (pintype "passive"))
      (node (ref "P2") (pin "1") (pinfunction "1_1") (pintype "passive"))
      (node (ref "RN4") (pin "5") (pinfunction "2_5") (pintype "passive"))
      (node (ref "RN4") (pin "6") (pinfunction "2_6") (pintype "passive"))
      (node (ref "RPR") (pin "2") (pinfunction "2_2") (pintype "passive"))
      (node (ref "RUSB") (pin "2") (pinfunction "2_2") (pintype "passive"))
      (node (ref "U1") (pin "4") (pinfunction "VCC_4") (pintype "bidirectional"))
    )
    (net (code "90") (name "unconnected-(IC2-OUT-Pad2)") (class "Default")
      (node (ref "IC2") (pin "2") (pinfunction "OUT_2") (pintype "bidirectional"))
    )
    (net (code "91") (name "unconnected-(IC3-SQW{slash}OUT-Pad7)") (class "Default")
      (node (ref "IC3") (pin "7") (pinfunction "SQW/OUT_7") (pintype "bidirectional"))
    )
    (net (code "92") (name "unconnected-(IC4-XTAL1-Pad8)") (class "Default")
      (node (ref "IC4") (pin "8") (pinfunction "XTAL1_8") (pintype "bidirectional"))
    )
    (net (code "93") (name "unconnected-(IC4-XTAL2-Pad7)") (class "Default")
      (node (ref "IC4") (pin "7") (pinfunction "XTAL2_7") (pintype "bidirectional"))
    )
    (net (code "94") (name "unconnected-(IC6-CLKOUT-Pad3)") (class "Default")
      (node (ref "IC6") (pin "3") (pinfunction "CLKOUT_3") (pintype "bidirectional"))
    )
    (net (code "95") (name "unconnected-(IC6-NC-Pad5)") (class "Default")
      (node (ref "IC6") (pin "5") (pinfunction "NC_5") (pintype "bidirectional"))
    )
    (net (code "96") (name "unconnected-(IC6-{slash}INT-Pad4)") (class "Default")
      (node (ref "IC6") (pin "4") (pinfunction "/INT_4") (pintype "bidirectional"))
    )
    (net (code "97") (name "unconnected-(J2-O-Pad1)") (class "Default")
      (node (ref "J2") (pin "1") (pinfunction "O_1") (pintype "passive"))
    )
    (net (code "98") (name "unconnected-(LCD-DB0-Pad7)") (class "Default")
      (node (ref "LCD") (pin "7") (pinfunction "DB0_7") (pintype "bidirectional"))
    )
    (net (code "99") (name "unconnected-(LCD-DB1-Pad8)") (class "Default")
      (node (ref "LCD") (pin "8") (pinfunction "DB1_8") (pintype "bidirectional"))
    )
    (net (code "100") (name "unconnected-(LCD-DB2-Pad9)") (class "Default")
      (node (ref "LCD") (pin "9") (pinfunction "DB2_9") (pintype "bidirectional"))
    )
    (net (code "101") (name "unconnected-(LCD-DB3-Pad10)") (class "Default")
      (node (ref "LCD") (pin "10") (pinfunction "DB3_10") (pintype "bidirectional"))
    )
    (net (code "102") (name "unconnected-(RJ45-PadNC)") (class "Default")
      (node (ref "RJ45") (pin "NC") (pinfunction "NC_NC") (pintype "bidirectional"))
    )
    (net (code "103") (name "unconnected-(RJ45-PadP5)") (class "Default")
      (node (ref "RJ45") (pin "P5") (pinfunction "P5_P5") (pintype "bidirectional"))
    )
    (net (code "104") (name "unconnected-(U1-NC-Pad1)") (class "Default")
      (node (ref "U1") (pin "1") (pinfunction "NC_1") (pintype "bidirectional"))
    )
    (net (code "105") (name "unconnected-(U1-RSV-Pad8)") (class "Default")
      (node (ref "U1") (pin "8") (pinfunction "RSV_8") (pintype "bidirectional"))
    )
  )
)
